# Gambar_Teknik_Sensor_Raihansyah_Akbar_M_.net
KiCad netlist of a schematic drawn in EAGLE
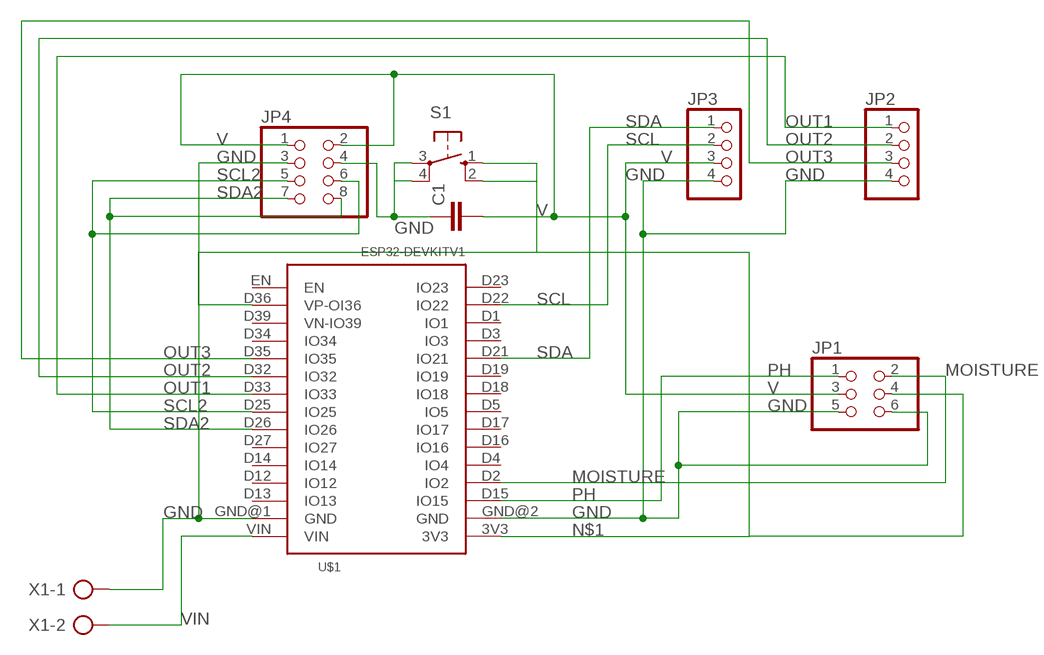
[diagram p0: schematic, sheet 1]

(export (version "E")
  (design (tool "Eeschema 10.0.6"))
  (components
    (comp (ref "C1")
      (value "C-EU050-030X075")
      (footprint "eagle-import:C050-030X075")
      (libsource (lib "eagle-import") (part "C-EU050-030X075"))
    )
    (comp (ref "JP1")
      (value "PINHD-2X3")
      (footprint "eagle-import:2X03")
      (libsource (lib "eagle-import") (part "PINHD-2X3"))
    )
    (comp (ref "JP2")
      (value "PINHD-1X4")
      (footprint "eagle-import:1X04")
      (libsource (lib "eagle-import") (part "PINHD-1X4"))
    )
    (comp (ref "JP3")
      (value "PINHD-1X4")
      (footprint "eagle-import:1X04")
      (libsource (lib "eagle-import") (part "PINHD-1X4"))
    )
    (comp (ref "JP4")
      (value "PINHD-2X4")
      (footprint "eagle-import:2X04")
      (libsource (lib "eagle-import") (part "PINHD-2X4"))
    )
    (comp (ref "S1")
      (value "10-XX")
      (footprint "eagle-import:B3F-10XX")
      (fields (field (name "MPN") "B3F-1000"))
      (libsource (lib "eagle-import") (part "10-XX"))
    )
    (comp (ref "U$1")
      (value "ESP32DEVKITV1")
      (footprint "eagle-import:ESP32-DEVKITV1")
      (libsource (lib "eagle-import") (part "ESP32DEVKITV1"))
    )
    (comp (ref "X1")
      (value "AK300/2")
      (footprint "eagle-import:AK300_2")
      (libsource (lib "eagle-import") (part "AK300/2"))
    )
  )
  (nets
    (net (code "1") (name "/GND") (class "Default")
      (node (ref "C1") (pin "1") (pinfunction "1_1") (pintype "passive"))
      (node (ref "JP1") (pin "5") (pinfunction "5_5") (pintype "passive"))
      (node (ref "JP1") (pin "6") (pinfunction "6_6") (pintype "passive"))
      (node (ref "JP2") (pin "4") (pinfunction "4_4") (pintype "passive"))
      (node (ref "JP3") (pin "4") (pinfunction "4_4") (pintype "passive"))
      (node (ref "JP4") (pin "3") (pinfunction "3_3") (pintype "passive"))
      (node (ref "JP4") (pin "4") (pinfunction "4_4") (pintype "passive"))
      (node (ref "S1") (pin "3") (pinfunction "P_3") (pintype "passive"))
      (node (ref "S1") (pin "4") (pinfunction "P1_4") (pintype "passive"))
      (node (ref "U$1") (pin "GND@1") (pinfunction "GND_GND@1") (pintype "bidirectional"))
      (node (ref "U$1") (pin "GND@2") (pinfunction "GND_GND@2") (pintype "bidirectional"))
      (node (ref "X1") (pin "1") (pinfunction "KL_1") (pintype "passive"))
    )
    (net (code "2") (name "/MOISTURE") (class "Default")
      (node (ref "JP1") (pin "2") (pinfunction "2_2") (pintype "passive"))
      (node (ref "U$1") (pin "D2") (pinfunction "IO2_D2") (pintype "bidirectional"))
    )
    (net (code "3") (name "/N$1") (class "Default")
      (node (ref "JP1") (pin "4") (pinfunction "4_4") (pintype "passive"))
      (node (ref "U$1") (pin "3V3") (pinfunction "3V3_3V3") (pintype "bidirectional"))
      (node (ref "U$1") (pin "D36") (pinfunction "VP-OI36_D36") (pintype "bidirectional"))
    )
    (net (code "4") (name "/OUT1") (class "Default")
      (node (ref "JP2") (pin "1") (pinfunction "1_1") (pintype "passive"))
      (node (ref "U$1") (pin "D33") (pinfunction "IO33_D33") (pintype "bidirectional"))
    )
    (net (code "5") (name "/OUT2") (class "Default")
      (node (ref "JP2") (pin "2") (pinfunction "2_2") (pintype "passive"))
      (node (ref "U$1") (pin "D32") (pinfunction "IO32_D32") (pintype "bidirectional"))
    )
    (net (code "6") (name "/OUT3") (class "Default")
      (node (ref "JP2") (pin "3") (pinfunction "3_3") (pintype "passive"))
      (node (ref "U$1") (pin "D35") (pinfunction "IO35_D35") (pintype "bidirectional"))
    )
    (net (code "7") (name "/PH") (class "Default")
      (node (ref "JP1") (pin "1") (pinfunction "1_1") (pintype "passive"))
      (node (ref "U$1") (pin "D15") (pinfunction "IO15_D15") (pintype "bidirectional"))
    )
    (net (code "8") (name "/SCL") (class "Default")
      (node (ref "JP3") (pin "2") (pinfunction "2_2") (pintype "passive"))
      (node (ref "U$1") (pin "D22") (pinfunction "IO22_D22") (pintype "bidirectional"))
    )
    (net (code "9") (name "/SCL2") (class "Default")
      (node (ref "JP4") (pin "5") (pinfunction "5_5") (pintype "passive"))
      (node (ref "JP4") (pin "6") (pinfunction "6_6") (pintype "passive"))
      (node (ref "U$1") (pin "D25") (pinfunction "IO25_D25") (pintype "bidirectional"))
    )
    (net (code "10") (name "/SDA") (class "Default")
      (node (ref "JP3") (pin "1") (pinfunction "1_1") (pintype "passive"))
      (node (ref "U$1") (pin "D21") (pinfunction "IO21_D21") (pintype "bidirectional"))
    )
    (net (code "11") (name "/SDA2") (class "Default")
      (node (ref "JP4") (pin "7") (pinfunction "7_7") (pintype "passive"))
      (node (ref "JP4") (pin "8") (pinfunction "8_8") (pintype "passive"))
      (node (ref "U$1") (pin "D26") (pinfunction "IO26_D26") (pintype "bidirectional"))
    )
    (net (code "12") (name "/V") (class "Default")
      (node (ref "C1") (pin "2") (pinfunction "2_2") (pintype "passive"))
      (node (ref "JP1") (pin "3") (pinfunction "3_3") (pintype "passive"))
      (node (ref "JP3") (pin "3") (pinfunction "3_3") (pintype "passive"))
      (node (ref "JP4") (pin "1") (pinfunction "1_1") (pintype "passive"))
      (node (ref "JP4") (pin "2") (pinfunction "2_2") (pintype "passive"))
      (node (ref "S1") (pin "1") (pinfunction "S_1") (pintype "passive"))
      (node (ref "S1") (pin "2") (pinfunction "S1_2") (pintype "passive"))
    )
    (net (code "13") (name "/VIN") (class "Default")
      (node (ref "U$1") (pin "VIN") (pinfunction "VIN_VIN") (pintype "bidirectional"))
      (node (ref "X1") (pin "2") (pinfunction "KL_2") (pintype "passive"))
    )
    (net (code "14") (name "unconnected-(U$1-IO1-PadD1)") (class "Default")
      (node (ref "U$1") (pin "D1") (pinfunction "IO1_D1") (pintype "bidirectional"))
    )
    (net (code "15") (name "unconnected-(U$1-IO3-PadD3)") (class "Default")
      (node (ref "U$1") (pin "D3") (pinfunction "IO3_D3") (pintype "bidirectional"))
    )
    (net (code "16") (name "unconnected-(U$1-IO4-PadD4)") (class "Default")
      (node (ref "U$1") (pin "D4") (pinfunction "IO4_D4") (pintype "bidirectional"))
    )
    (net (code "17") (name "unconnected-(U$1-IO5-PadD5)") (class "Default")
      (node (ref "U$1") (pin "D5") (pinfunction "IO5_D5") (pintype "bidirectional"))
    )
    (net (code "18") (name "unconnected-(U$1-IO12-PadD12)") (class "Default")
      (node (ref "U$1") (pin "D12") (pinfunction "IO12_D12") (pintype "bidirectional"))
    )
    (net (code "19") (name "unconnected-(U$1-IO13-PadD13)") (class "Default")
      (node (ref "U$1") (pin "D13") (pinfunction "IO13_D13") (pintype "bidirectional"))
    )
    (net (code "20") (name "unconnected-(U$1-IO14-PadD14)") (class "Default")
      (node (ref "U$1") (pin "D14") (pinfunction "IO14_D14") (pintype "bidirectional"))
    )
    (net (code "21") (name "unconnected-(U$1-IO16-PadD16)") (class "Default")
      (node (ref "U$1") (pin "D16") (pinfunction "IO16_D16") (pintype "bidirectional"))
    )
    (net (code "22") (name "unconnected-(U$1-IO17-PadD17)") (class "Default")
      (node (ref "U$1") (pin "D17") (pinfunction "IO17_D17") (pintype "bidirectional"))
    )
    (net (code "23") (name "unconnected-(U$1-IO18-PadD18)") (class "Default")
      (node (ref "U$1") (pin "D18") (pinfunction "IO18_D18") (pintype "bidirectional"))
    )
    (net (code "24") (name "unconnected-(U$1-IO19-PadD19)") (class "Default")
      (node (ref "U$1") (pin "D19") (pinfunction "IO19_D19") (pintype "bidirectional"))
    )
    (net (code "25") (name "unconnected-(U$1-IO23-PadD23)") (class "Default")
      (node (ref "U$1") (pin "D23") (pinfunction "IO23_D23") (pintype "bidirectional"))
    )
    (net (code "26") (name "unconnected-(U$1-IO27-PadD27)") (class "Default")
      (node (ref "U$1") (pin "D27") (pinfunction "IO27_D27") (pintype "bidirectional"))
    )
    (net (code "27") (name "unconnected-(U$1-IO34-PadD34)") (class "Default")
      (node (ref "U$1") (pin "D34") (pinfunction "IO34_D34") (pintype "bidirectional"))
    )
    (net (code "28") (name "unconnected-(U$1-PadEN)") (class "Default")
      (node (ref "U$1") (pin "EN") (pinfunction "EN_EN") (pintype "bidirectional"))
    )
    (net (code "29") (name "unconnected-(U$1-VN-IO39-PadD39)") (class "Default")
      (node (ref "U$1") (pin "D39") (pinfunction "VN-IO39_D39") (pintype "bidirectional"))
    )
  )
)
